# main.net
KiCad netlist of a schematic drawn in EAGLE
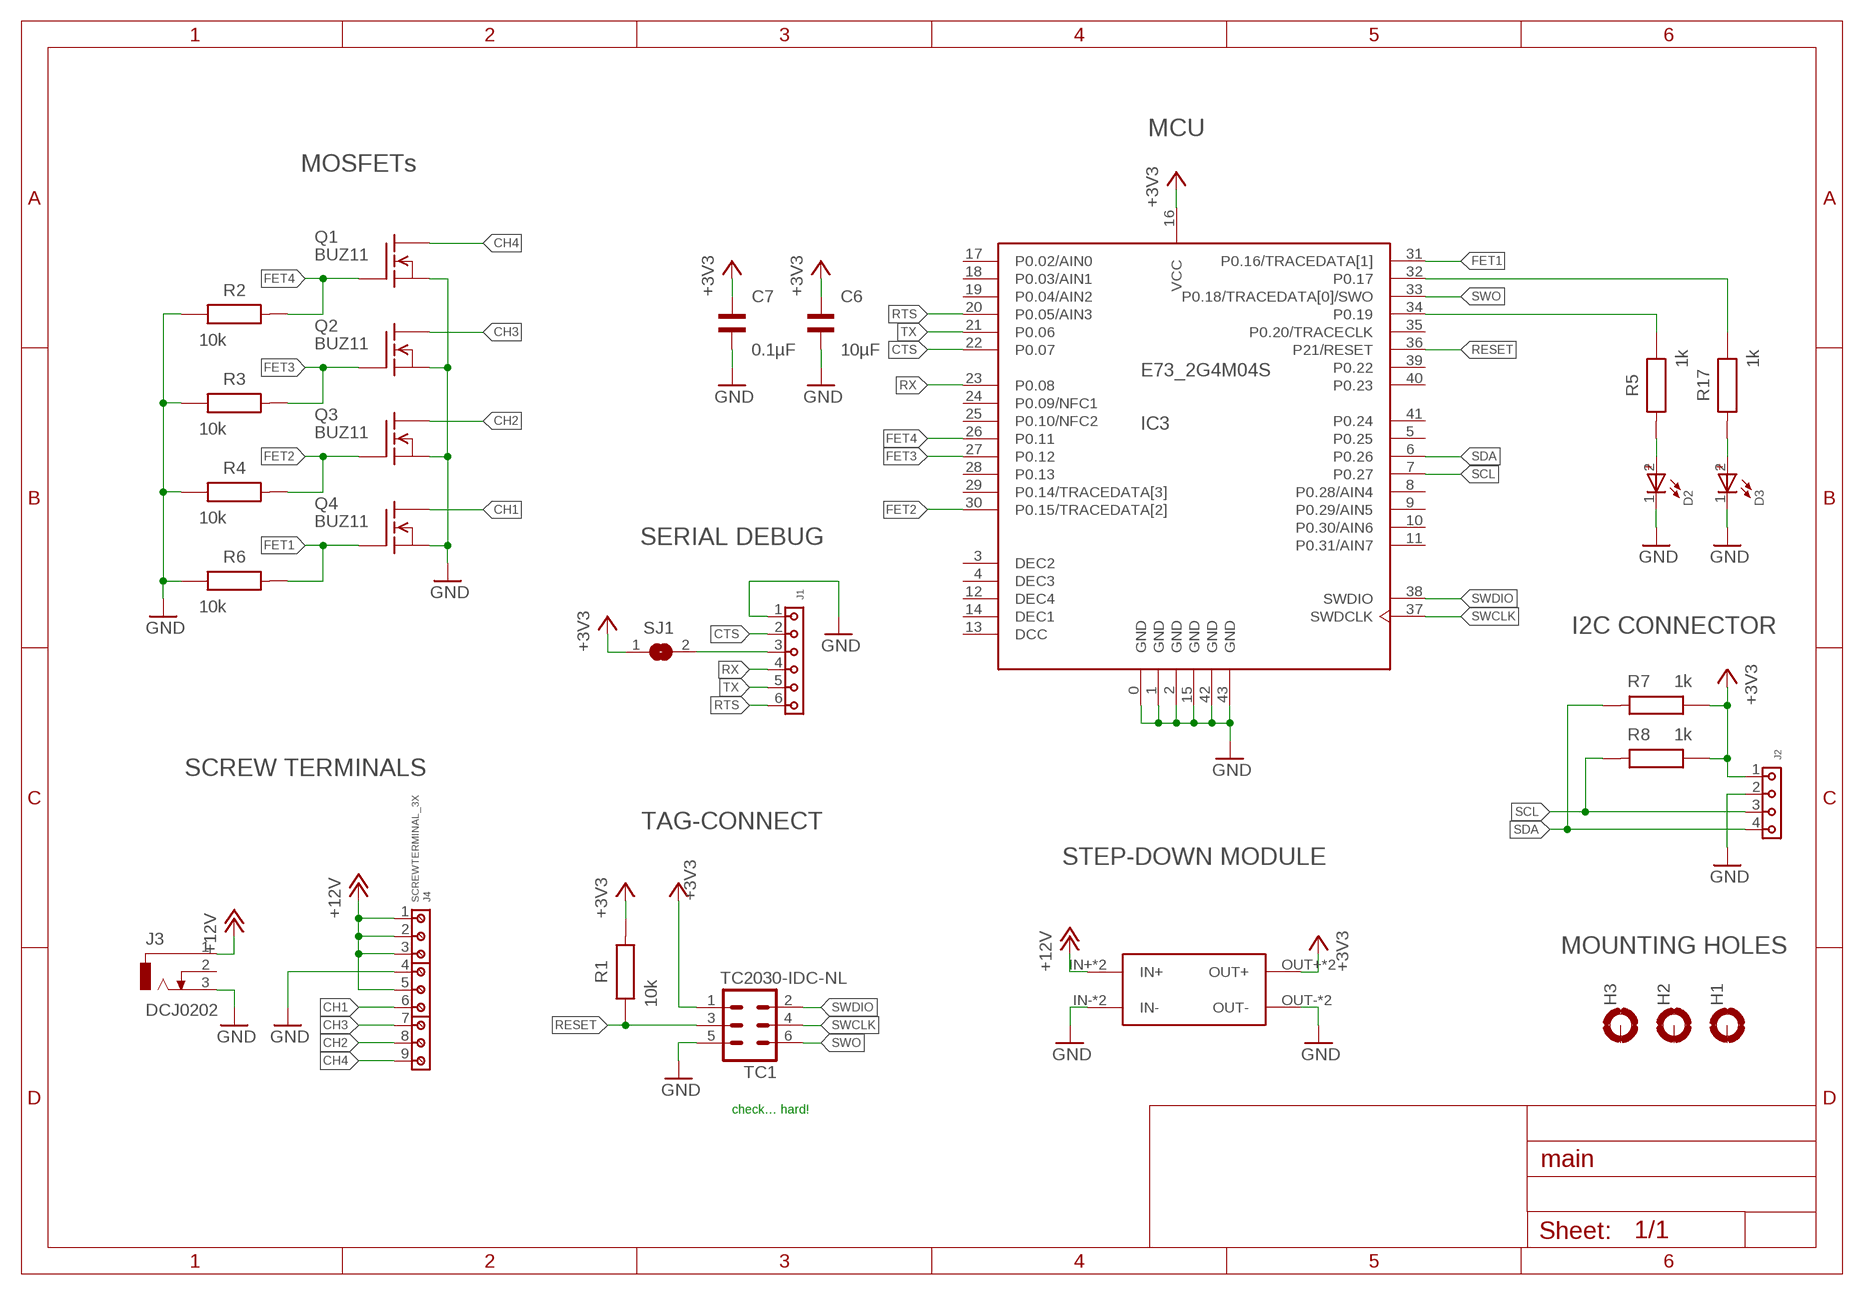
[diagram p0: schematic, sheet 1]

(export (version "E")
  (design (tool "Eeschema 10.0.6"))
  (components
    (comp (ref "C6")
      (value "10µF")
      (footprint "eagle-import:WCAP-CSGP_0603_REFLOW")
      (libsource (lib "eagle-import") (part "WCAP-CSGP_0603_REFLOW_885012206046"))
    )
    (comp (ref "C7")
      (value "0.1µF")
      (footprint "eagle-import:WCAP-CSGP_0603_REFLOW")
      (libsource (lib "eagle-import") (part "WCAP-CSGP_0603_REFLOW_885012206046"))
    )
    (comp (ref "D2")
      (value "WL-SMCW_0603_150060BS75000")
      (footprint "eagle-import:WL-SMCW_0603")
      (libsource (lib "eagle-import") (part "WL-SMCW_0603_150060BS75000"))
    )
    (comp (ref "D3")
      (value "WL-SMCW_0603_150060BS75000")
      (footprint "eagle-import:WL-SMCW_0603")
      (libsource (lib "eagle-import") (part "WL-SMCW_0603_150060BS75000"))
    )
    (comp (ref "H1")
      (value "MOUNT-PAD-ROUND3.2")
      (footprint "eagle-import:3,2-PAD")
      (libsource (lib "eagle-import") (part "MOUNT-PAD-ROUND3.2"))
    )
    (comp (ref "H2")
      (value "MOUNT-PAD-ROUND3.2")
      (footprint "eagle-import:3,2-PAD")
      (libsource (lib "eagle-import") (part "MOUNT-PAD-ROUND3.2"))
    )
    (comp (ref "H3")
      (value "MOUNT-PAD-ROUND3.2")
      (footprint "eagle-import:3,2-PAD")
      (libsource (lib "eagle-import") (part "MOUNT-PAD-ROUND3.2"))
    )
    (comp (ref "IC3")
      (value "E73_2G4M04S")
      (footprint "eagle-import:E73_2G4M04S")
      (libsource (lib "eagle-import") (part "E73_2G4M04S"))
    )
    (comp (ref "J1")
      (value "6130XX11821_61300611821")
      (footprint "eagle-import:61300611821")
      (libsource (lib "eagle-import") (part "6130XX11821_61300611821"))
    )
    (comp (ref "J2")
      (value "6130XX11821_61300411821")
      (footprint "eagle-import:61300411821")
      (libsource (lib "eagle-import") (part "6130XX11821_61300411821"))
    )
    (comp (ref "J3")
      (value "DCJ0202")
      (footprint "eagle-import:DCJ0202")
      (libsource (lib "eagle-import") (part "DCJ0202"))
    )
    (comp (ref "J4")
      (value "SCREWTERMINAL_3X")
      (footprint "eagle-import:691102710003")
      (libsource (lib "eagle-import") (part "SCREWTERMINAL_3X"))
    )
    (comp (ref "Q1")
      (value "BUZ11")
      (footprint "eagle-import:TO220")
      (libsource (lib "eagle-import") (part "BUZ11"))
    )
    (comp (ref "Q2")
      (value "BUZ11")
      (footprint "eagle-import:TO220")
      (libsource (lib "eagle-import") (part "BUZ11"))
    )
    (comp (ref "Q3")
      (value "BUZ11")
      (footprint "eagle-import:TO220")
      (libsource (lib "eagle-import") (part "BUZ11"))
    )
    (comp (ref "Q4")
      (value "BUZ11")
      (footprint "eagle-import:TO220")
      (libsource (lib "eagle-import") (part "BUZ11"))
    )
    (comp (ref "R1")
      (value "10k")
      (footprint "eagle-import:WRIS-PSMB_0603_1.6X0.8X0.35X0.6(LXWXHXPW)")
      (libsource (lib "eagle-import") (part "WRIS-PSMB_0603_1.6X0.8X0.35X0.6_580060716001"))
    )
    (comp (ref "R2")
      (value "10k")
      (footprint "eagle-import:WRIS-PSMB_0603_1.6X0.8X0.35X0.6(LXWXHXPW)")
      (libsource (lib "eagle-import") (part "WRIS-PSMB_0603_1.6X0.8X0.35X0.6_580060716001"))
    )
    (comp (ref "R3")
      (value "10k")
      (footprint "eagle-import:WRIS-PSMB_0603_1.6X0.8X0.35X0.6(LXWXHXPW)")
      (libsource (lib "eagle-import") (part "WRIS-PSMB_0603_1.6X0.8X0.35X0.6_580060716001"))
    )
    (comp (ref "R4")
      (value "10k")
      (footprint "eagle-import:WRIS-PSMB_0603_1.6X0.8X0.35X0.6(LXWXHXPW)")
      (libsource (lib "eagle-import") (part "WRIS-PSMB_0603_1.6X0.8X0.35X0.6_580060716001"))
    )
    (comp (ref "R5")
      (value "1k")
      (footprint "eagle-import:WRIS-PSMB_0603_1.6X0.8X0.35X0.6(LXWXHXPW)")
      (libsource (lib "eagle-import") (part "WRIS-PSMB_0603_1.6X0.8X0.35X0.6_580060716001"))
    )
    (comp (ref "R6")
      (value "10k")
      (footprint "eagle-import:WRIS-PSMB_0603_1.6X0.8X0.35X0.6(LXWXHXPW)")
      (libsource (lib "eagle-import") (part "WRIS-PSMB_0603_1.6X0.8X0.35X0.6_580060716001"))
    )
    (comp (ref "R7")
      (value "1k")
      (footprint "eagle-import:WRIS-PSMB_0603_1.6X0.8X0.35X0.6(LXWXHXPW)")
      (libsource (lib "eagle-import") (part "WRIS-PSMB_0603_1.6X0.8X0.35X0.6_580060716001"))
    )
    (comp (ref "R8")
      (value "1k")
      (footprint "eagle-import:WRIS-PSMB_0603_1.6X0.8X0.35X0.6(LXWXHXPW)")
      (libsource (lib "eagle-import") (part "WRIS-PSMB_0603_1.6X0.8X0.35X0.6_580060716001"))
    )
    (comp (ref "R17")
      (value "1k")
      (footprint "eagle-import:WRIS-PSMB_0603_1.6X0.8X0.35X0.6(LXWXHXPW)")
      (libsource (lib "eagle-import") (part "WRIS-PSMB_0603_1.6X0.8X0.35X0.6_580060716001"))
    )
    (comp (ref "SJ1") (value "SJ") (footprint "eagle-import:SJ") (libsource (lib "eagle-import") (part "SJ")))
    (comp (ref "TC1")
      (value "TC2030-IDC-NL")
      (footprint "eagle-import:TC2030-IDC-NL")
      (libsource (lib "eagle-import") (part "TC2030-IDC-NL"))
    )
    (comp (ref "U$1")
      (value "LM2596-MODULE")
      (footprint "eagle-import:LM2596-MODULE")
      (libsource (lib "eagle-import") (part "LM2596-MODULE"))
    )
  )
  (nets
    (net (code "1") (name "+3V3") (class "Default")
      (node (ref "C6") (pin "2") (pinfunction "2_2") (pintype "passive"))
      (node (ref "C7") (pin "2") (pinfunction "2_2") (pintype "passive"))
      (node (ref "IC3") (pin "16") (pinfunction "VCC_16") (pintype "passive"))
      (node (ref "J2") (pin "1") (pinfunction "1_1") (pintype "passive"))
      (node (ref "R1") (pin "2") (pinfunction "2_2") (pintype "passive"))
      (node (ref "R7") (pin "1") (pinfunction "1_1") (pintype "passive"))
      (node (ref "R8") (pin "1") (pinfunction "1_1") (pintype "passive"))
      (node (ref "SJ1") (pin "1") (pinfunction "1_1") (pintype "passive"))
      (node (ref "TC1") (pin "1") (pinfunction "1_1") (pintype "passive"))
      (node (ref "U$1") (pin "OUT+") (pinfunction "OUT+_OUT+") (pintype "bidirectional"))
      (node (ref "U$1") (pin "OUT+1") (pinfunction "OUT+_OUT+1") (pintype "bidirectional"))
    )
    (net (code "2") (name "+12V") (class "Default")
      (node (ref "J3") (pin "1") (pinfunction "1_1") (pintype "passive"))
      (node (ref "J4") (pin "1") (pinfunction "1_1") (pintype "passive"))
      (node (ref "J4") (pin "2") (pinfunction "2_2") (pintype "passive"))
      (node (ref "J4") (pin "3") (pinfunction "3_3") (pintype "passive"))
      (node (ref "J4") (pin "5") (pinfunction "5_5") (pintype "passive"))
      (node (ref "U$1") (pin "IN+") (pinfunction "IN+_IN+") (pintype "bidirectional"))
      (node (ref "U$1") (pin "IN+1") (pinfunction "IN+_IN+1") (pintype "bidirectional"))
    )
    (net (code "3") (name "/DCC") (class "Default")
      (node (ref "IC3") (pin "13") (pinfunction "DCC_13") (pintype "power_in"))
    )
    (net (code "4") (name "/DEC1") (class "Default")
      (node (ref "IC3") (pin "14") (pinfunction "DEC1_14") (pintype "power_in"))
    )
    (net (code "5") (name "/DEC2") (class "Default")
      (node (ref "IC3") (pin "3") (pinfunction "DEC2_3") (pintype "power_in"))
    )
    (net (code "6") (name "/DEC3") (class "Default")
      (node (ref "IC3") (pin "4") (pinfunction "DEC3_4") (pintype "power_in"))
    )
    (net (code "7") (name "/DEC4") (class "Default")
      (node (ref "IC3") (pin "12") (pinfunction "DEC4_12") (pintype "power_in"))
    )
    (net (code "8") (name "CH1") (class "Default")
      (node (ref "J4") (pin "6") (pinfunction "6_6") (pintype "passive"))
      (node (ref "Q4") (pin "2") (pinfunction "D_2") (pintype "passive"))
    )
    (net (code "9") (name "CH2") (class "Default")
      (node (ref "J4") (pin "8") (pinfunction "8_8") (pintype "passive"))
      (node (ref "Q3") (pin "2") (pinfunction "D_2") (pintype "passive"))
    )
    (net (code "10") (name "CH3") (class "Default")
      (node (ref "J4") (pin "7") (pinfunction "7_7") (pintype "passive"))
      (node (ref "Q2") (pin "2") (pinfunction "D_2") (pintype "passive"))
    )
    (net (code "11") (name "CH4") (class "Default")
      (node (ref "J4") (pin "9") (pinfunction "9_9") (pintype "passive"))
      (node (ref "Q1") (pin "2") (pinfunction "D_2") (pintype "passive"))
    )
    (net (code "12") (name "CTS") (class "Default")
      (node (ref "IC3") (pin "22") (pinfunction "P0.07_22") (pintype "bidirectional"))
      (node (ref "J1") (pin "2") (pinfunction "2_2") (pintype "passive"))
    )
    (net (code "13") (name "FET1") (class "Default")
      (node (ref "IC3") (pin "31") (pinfunction "P0.16/TRACEDATA[1]_31") (pintype "bidirectional"))
      (node (ref "Q4") (pin "1") (pinfunction "G_1") (pintype "passive"))
      (node (ref "R6") (pin "2") (pinfunction "2_2") (pintype "passive"))
    )
    (net (code "14") (name "FET2") (class "Default")
      (node (ref "IC3") (pin "30") (pinfunction "P0.15/TRACEDATA[2]_30") (pintype "bidirectional"))
      (node (ref "Q3") (pin "1") (pinfunction "G_1") (pintype "passive"))
      (node (ref "R4") (pin "2") (pinfunction "2_2") (pintype "passive"))
    )
    (net (code "15") (name "FET3") (class "Default")
      (node (ref "IC3") (pin "27") (pinfunction "P0.12_27") (pintype "bidirectional"))
      (node (ref "Q2") (pin "1") (pinfunction "G_1") (pintype "passive"))
      (node (ref "R3") (pin "2") (pinfunction "2_2") (pintype "passive"))
    )
    (net (code "16") (name "FET4") (class "Default")
      (node (ref "IC3") (pin "26") (pinfunction "P0.11_26") (pintype "bidirectional"))
      (node (ref "Q1") (pin "1") (pinfunction "G_1") (pintype "passive"))
      (node (ref "R2") (pin "2") (pinfunction "2_2") (pintype "passive"))
    )
    (net (code "17") (name "GND") (class "Default")
      (node (ref "C6") (pin "1") (pinfunction "1_1") (pintype "passive"))
      (node (ref "C7") (pin "1") (pinfunction "1_1") (pintype "passive"))
      (node (ref "D2") (pin "1") (pinfunction "-_1") (pintype "passive"))
      (node (ref "D3") (pin "1") (pinfunction "-_1") (pintype "passive"))
      (node (ref "IC3") (pin "0") (pinfunction "GND_0") (pintype "bidirectional"))
      (node (ref "IC3") (pin "1") (pinfunction "GND_1") (pintype "bidirectional"))
      (node (ref "IC3") (pin "15") (pinfunction "GND_15") (pintype "bidirectional"))
      (node (ref "IC3") (pin "2") (pinfunction "GND_2") (pintype "bidirectional"))
      (node (ref "IC3") (pin "42") (pinfunction "GND_42") (pintype "bidirectional"))
      (node (ref "IC3") (pin "43") (pinfunction "GND_43") (pintype "bidirectional"))
      (node (ref "J1") (pin "1") (pinfunction "1_1") (pintype "passive"))
      (node (ref "J2") (pin "2") (pinfunction "2_2") (pintype "passive"))
      (node (ref "J3") (pin "3") (pinfunction "3_3") (pintype "passive"))
      (node (ref "J4") (pin "4") (pinfunction "4_4") (pintype "passive"))
      (node (ref "Q1") (pin "3") (pinfunction "S_3") (pintype "passive"))
      (node (ref "Q2") (pin "3") (pinfunction "S_3") (pintype "passive"))
      (node (ref "Q3") (pin "3") (pinfunction "S_3") (pintype "passive"))
      (node (ref "Q4") (pin "3") (pinfunction "S_3") (pintype "passive"))
      (node (ref "R2") (pin "1") (pinfunction "1_1") (pintype "passive"))
      (node (ref "R3") (pin "1") (pinfunction "1_1") (pintype "passive"))
      (node (ref "R4") (pin "1") (pinfunction "1_1") (pintype "passive"))
      (node (ref "R6") (pin "1") (pinfunction "1_1") (pintype "passive"))
      (node (ref "TC1") (pin "5") (pinfunction "5_5") (pintype "passive"))
      (node (ref "U$1") (pin "IN-") (pinfunction "IN-_IN-") (pintype "bidirectional"))
      (node (ref "U$1") (pin "IN-1") (pinfunction "IN-_IN-1") (pintype "bidirectional"))
      (node (ref "U$1") (pin "OUT-") (pinfunction "OUT-_OUT-") (pintype "bidirectional"))
      (node (ref "U$1") (pin "OUT-1") (pinfunction "OUT-_OUT-1") (pintype "bidirectional"))
    )
    (net (code "18") (name "Net-(D2-+)") (class "Default")
      (node (ref "D2") (pin "2") (pinfunction "+_2") (pintype "passive"))
      (node (ref "R5") (pin "2") (pinfunction "2_2") (pintype "passive"))
    )
    (net (code "19") (name "Net-(D3-+)") (class "Default")
      (node (ref "D3") (pin "2") (pinfunction "+_2") (pintype "passive"))
      (node (ref "R17") (pin "2") (pinfunction "2_2") (pintype "passive"))
    )
    (net (code "20") (name "Net-(IC3-P0.17)") (class "Default")
      (node (ref "IC3") (pin "32") (pinfunction "P0.17_32") (pintype "bidirectional"))
      (node (ref "R17") (pin "1") (pinfunction "1_1") (pintype "passive"))
    )
    (net (code "21") (name "Net-(IC3-P0.19)") (class "Default")
      (node (ref "IC3") (pin "34") (pinfunction "P0.19_34") (pintype "bidirectional"))
      (node (ref "R5") (pin "1") (pinfunction "1_1") (pintype "passive"))
    )
    (net (code "22") (name "Net-(J1-Pad3)") (class "Default")
      (node (ref "J1") (pin "3") (pinfunction "3_3") (pintype "passive"))
      (node (ref "SJ1") (pin "2") (pinfunction "2_2") (pintype "passive"))
    )
    (net (code "23") (name "RESET") (class "Default")
      (node (ref "IC3") (pin "36") (pinfunction "P21/RESET_36") (pintype "bidirectional"))
      (node (ref "R1") (pin "1") (pinfunction "1_1") (pintype "passive"))
      (node (ref "TC1") (pin "3") (pinfunction "3_3") (pintype "passive"))
    )
    (net (code "24") (name "RTS") (class "Default")
      (node (ref "IC3") (pin "20") (pinfunction "P0.05/AIN3_20") (pintype "bidirectional"))
      (node (ref "J1") (pin "6") (pinfunction "6_6") (pintype "passive"))
    )
    (net (code "25") (name "RX") (class "Default")
      (node (ref "IC3") (pin "23") (pinfunction "P0.08_23") (pintype "bidirectional"))
      (node (ref "J1") (pin "4") (pinfunction "4_4") (pintype "passive"))
    )
    (net (code "26") (name "SCL") (class "Default")
      (node (ref "IC3") (pin "7") (pinfunction "P0.27_7") (pintype "bidirectional"))
      (node (ref "J2") (pin "3") (pinfunction "3_3") (pintype "passive"))
      (node (ref "R8") (pin "2") (pinfunction "2_2") (pintype "passive"))
    )
    (net (code "27") (name "SDA") (class "Default")
      (node (ref "IC3") (pin "6") (pinfunction "P0.26_6") (pintype "bidirectional"))
      (node (ref "J2") (pin "4") (pinfunction "4_4") (pintype "passive"))
      (node (ref "R7") (pin "2") (pinfunction "2_2") (pintype "passive"))
    )
    (net (code "28") (name "SWCLK") (class "Default")
      (node (ref "IC3") (pin "37") (pinfunction "SWDCLK_37") (pintype "input"))
      (node (ref "TC1") (pin "4") (pinfunction "4_4") (pintype "passive"))
    )
    (net (code "29") (name "SWDIO") (class "Default")
      (node (ref "IC3") (pin "38") (pinfunction "SWDIO_38") (pintype "bidirectional"))
      (node (ref "TC1") (pin "2") (pinfunction "2_2") (pintype "passive"))
    )
    (net (code "30") (name "SWO") (class "Default")
      (node (ref "IC3") (pin "33") (pinfunction "P0.18/TRACEDATA[0]/SWO_33") (pintype "bidirectional"))
      (node (ref "TC1") (pin "6") (pinfunction "6_6") (pintype "passive"))
    )
    (net (code "31") (name "TX") (class "Default")
      (node (ref "IC3") (pin "21") (pinfunction "P0.06_21") (pintype "bidirectional"))
      (node (ref "J1") (pin "5") (pinfunction "5_5") (pintype "passive"))
    )
    (net (code "32") (name "unconnected-(H1-MOUNT-PadB3,2)") (class "Default")
      (node (ref "H1") (pin "B3,2") (pinfunction "MOUNT_B3,2") (pintype "passive"))
    )
    (net (code "33") (name "unconnected-(H2-MOUNT-PadB3,2)") (class "Default")
      (node (ref "H2") (pin "B3,2") (pinfunction "MOUNT_B3,2") (pintype "passive"))
    )
    (net (code "34") (name "unconnected-(H3-MOUNT-PadB3,2)") (class "Default")
      (node (ref "H3") (pin "B3,2") (pinfunction "MOUNT_B3,2") (pintype "passive"))
    )
    (net (code "35") (name "unconnected-(IC3-P0.02{slash}AIN0-Pad17)") (class "Default")
      (node (ref "IC3") (pin "17") (pinfunction "P0.02/AIN0_17") (pintype "bidirectional"))
    )
    (net (code "36") (name "unconnected-(IC3-P0.03{slash}AIN1-Pad18)") (class "Default")
      (node (ref "IC3") (pin "18") (pinfunction "P0.03/AIN1_18") (pintype "bidirectional"))
    )
    (net (code "37") (name "unconnected-(IC3-P0.04{slash}AIN2-Pad19)") (class "Default")
      (node (ref "IC3") (pin "19") (pinfunction "P0.04/AIN2_19") (pintype "bidirectional"))
    )
    (net (code "38") (name "unconnected-(IC3-P0.09{slash}NFC1-Pad24)") (class "Default")
      (node (ref "IC3") (pin "24") (pinfunction "P0.09/NFC1_24") (pintype "bidirectional"))
    )
    (net (code "39") (name "unconnected-(IC3-P0.10{slash}NFC2-Pad25)") (class "Default")
      (node (ref "IC3") (pin "25") (pinfunction "P0.10/NFC2_25") (pintype "bidirectional"))
    )
    (net (code "40") (name "unconnected-(IC3-P0.13-Pad28)") (class "Default")
      (node (ref "IC3") (pin "28") (pinfunction "P0.13_28") (pintype "bidirectional"))
    )
    (net (code "41") (name "unconnected-(IC3-P0.14{slash}TRACEDATA[3]-Pad29)") (class "Default")
      (node (ref "IC3") (pin "29") (pinfunction "P0.14/TRACEDATA[3]_29") (pintype "bidirectional"))
    )
    (net (code "42") (name "unconnected-(IC3-P0.20{slash}TRACECLK-Pad35)") (class "Default")
      (node (ref "IC3") (pin "35") (pinfunction "P0.20/TRACECLK_35") (pintype "bidirectional"))
    )
    (net (code "43") (name "unconnected-(IC3-P0.22-Pad39)") (class "Default")
      (node (ref "IC3") (pin "39") (pinfunction "P0.22_39") (pintype "bidirectional"))
    )
    (net (code "44") (name "unconnected-(IC3-P0.23-Pad40)") (class "Default")
      (node (ref "IC3") (pin "40") (pinfunction "P0.23_40") (pintype "bidirectional"))
    )
    (net (code "45") (name "unconnected-(IC3-P0.24-Pad41)") (class "Default")
      (node (ref "IC3") (pin "41") (pinfunction "P0.24_41") (pintype "bidirectional"))
    )
    (net (code "46") (name "unconnected-(IC3-P0.25-Pad5)") (class "Default")
      (node (ref "IC3") (pin "5") (pinfunction "P0.25_5") (pintype "bidirectional"))
    )
    (net (code "47") (name "unconnected-(IC3-P0.28{slash}AIN4-Pad8)") (class "Default")
      (node (ref "IC3") (pin "8") (pinfunction "P0.28/AIN4_8") (pintype "bidirectional"))
    )
    (net (code "48") (name "unconnected-(IC3-P0.29{slash}AIN5-Pad9)") (class "Default")
      (node (ref "IC3") (pin "9") (pinfunction "P0.29/AIN5_9") (pintype "bidirectional"))
    )
    (net (code "49") (name "unconnected-(IC3-P0.30{slash}AIN6-Pad10)") (class "Default")
      (node (ref "IC3") (pin "10") (pinfunction "P0.30/AIN6_10") (pintype "bidirectional"))
    )
    (net (code "50") (name "unconnected-(IC3-P0.31{slash}AIN7-Pad11)") (class "Default")
      (node (ref "IC3") (pin "11") (pinfunction "P0.31/AIN7_11") (pintype "bidirectional"))
    )
    (net (code "51") (name "unconnected-(J3-Pad2)") (class "Default")
      (node (ref "J3") (pin "2") (pinfunction "2_2") (pintype "passive"))
    )
  )
)
